# BW1097_BootSel.net
KiCad netlist of a schematic drawn in Altium Designer
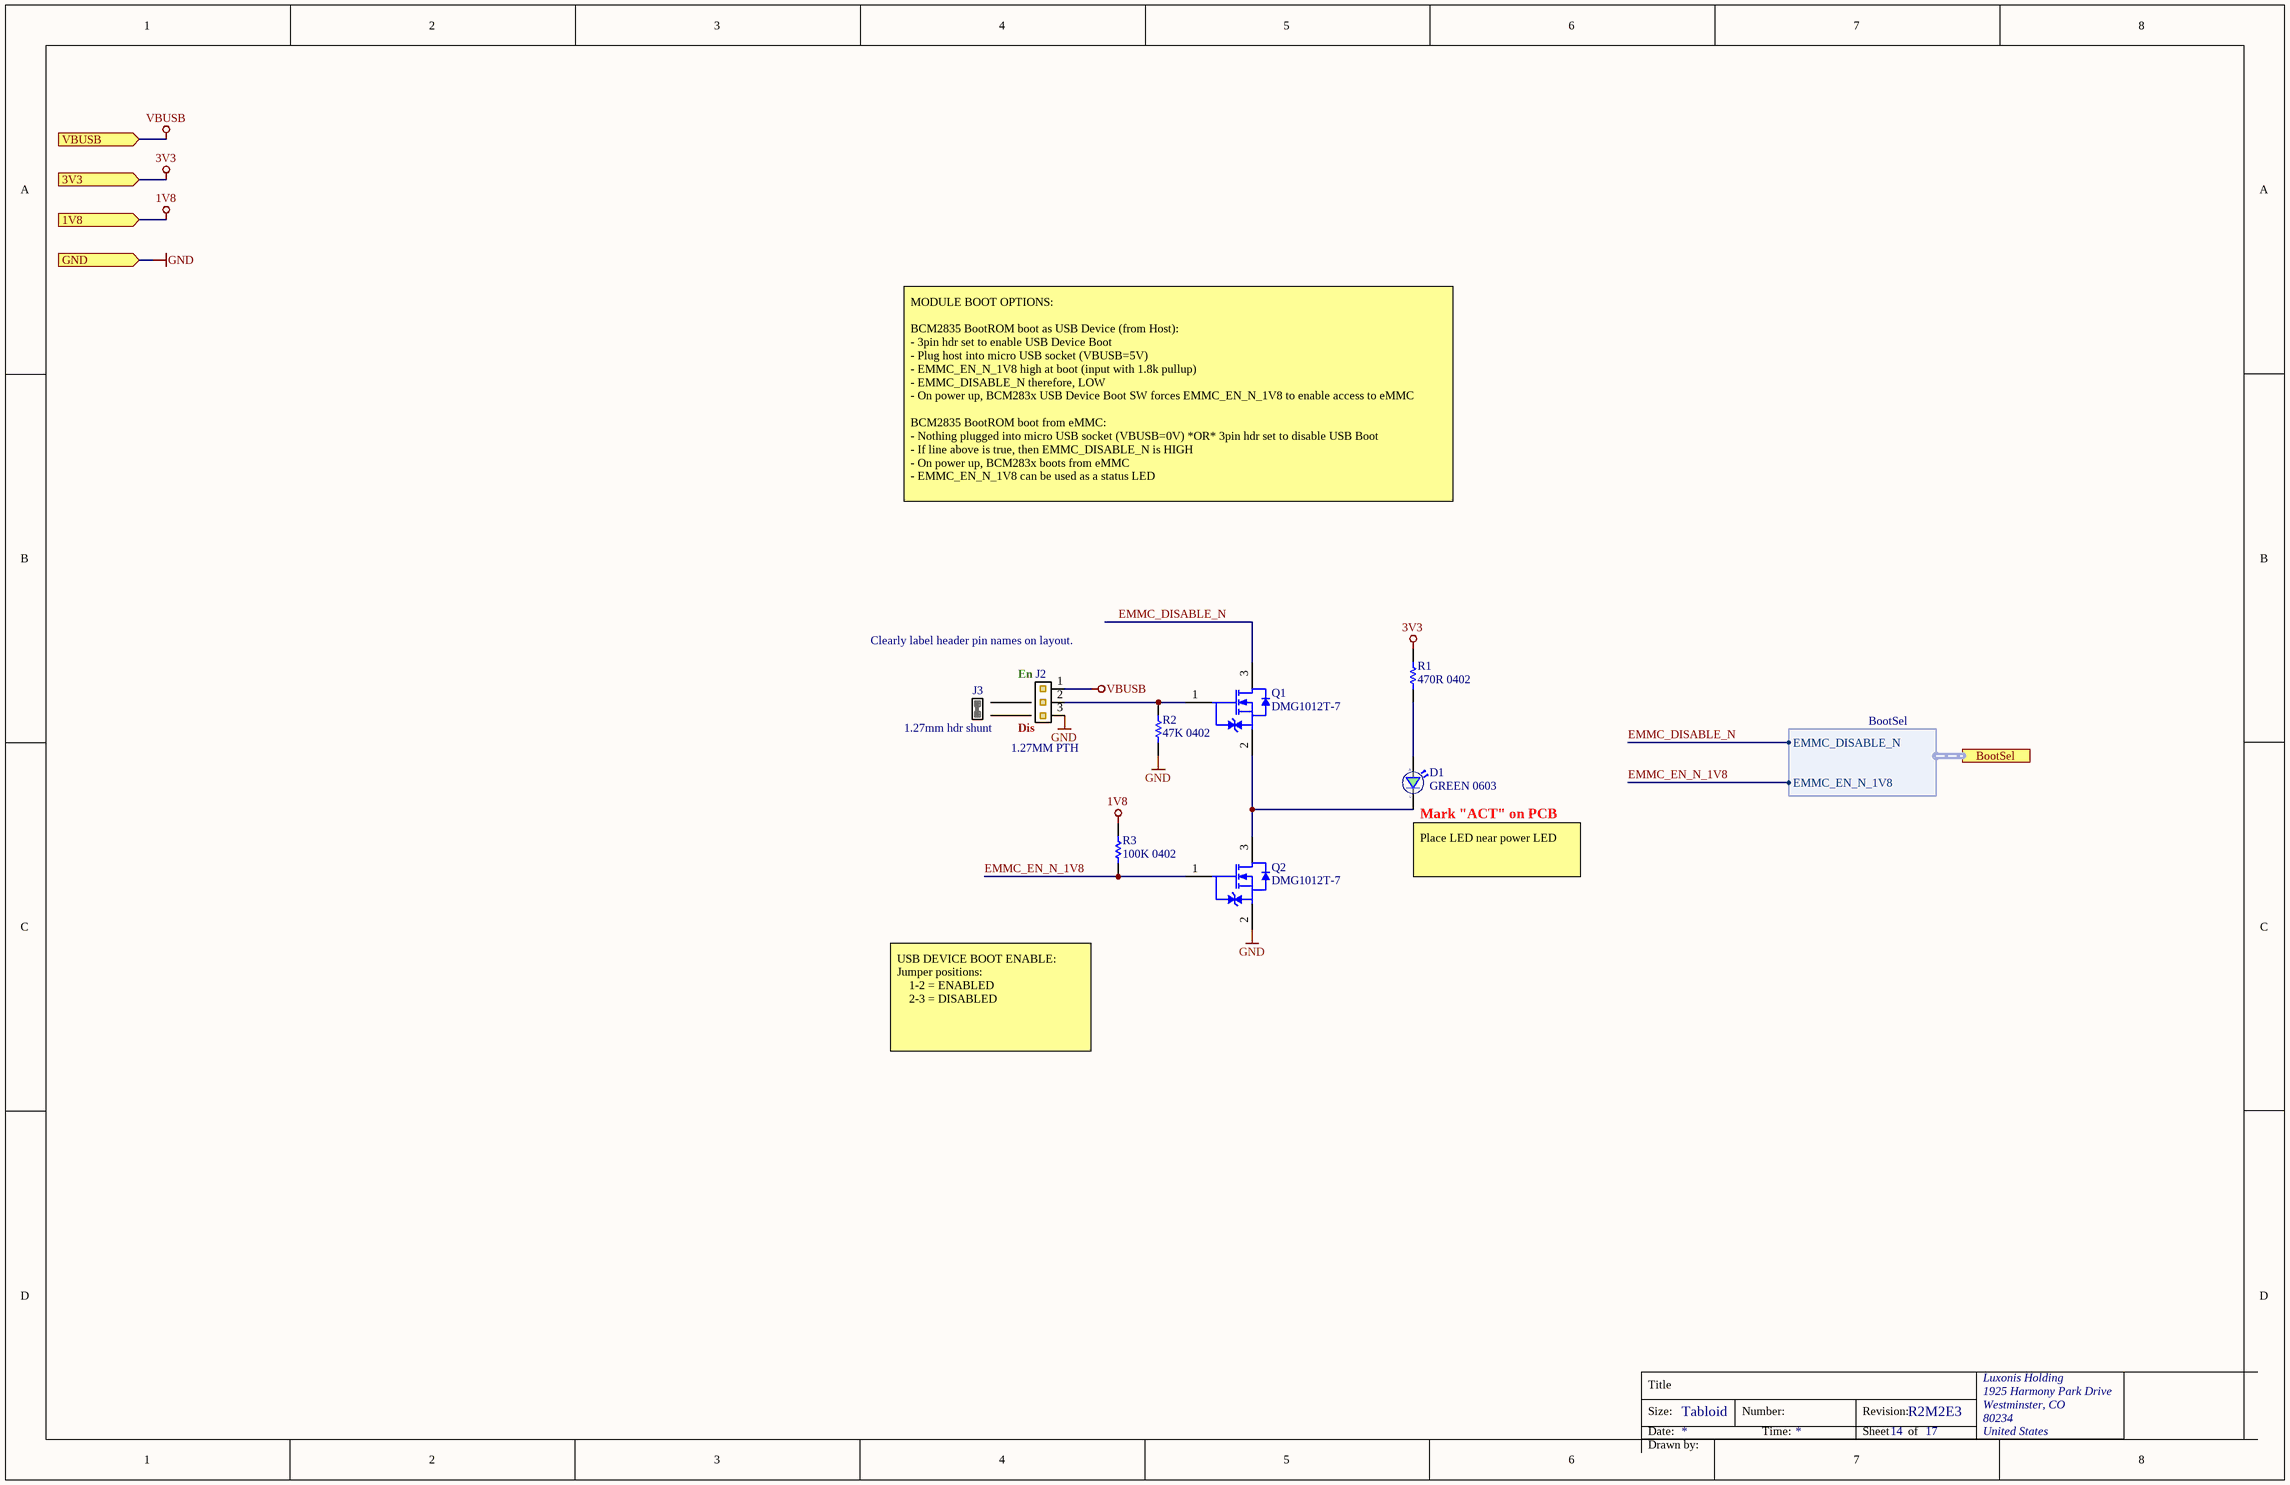
[diagram p0: BW1097_BootSel.SchDoc]

(export (version "E")
  (design (tool "Eeschema 10.0.6"))
  (components
    (comp (ref "D1")
      (value "GREEN 0603")
      (footprint "LuxonisMaster:SML_D1xx8W")
      (description "LED GREEN DIFFUSED 0603 SMD Green 572nm LED Indication - Discrete 2.2V 0603 (1608 Metric)")
      (fields (field (name "MANUFACTURER") "Rohm") (field (name "MANUFACTURER PART NUMBER") "SML-D12M8WT86"))
      (libsource (lib "LuxonisMaster") (part "SML-D12M8WT86"))
    )
    (comp (ref "J2")
      (value "1.27MM PTH")
      (footprint "LuxonisMaster:GRPB031VWVN-RC")
      (description "CONN HEADER VERT 3POS 1.27MM")
      (libsource (lib "LuxonisMaster") (part "GRPB031VWVN-RC"))
    )
    (comp (ref "J3")
      (value "1.27mm hdr shunt")
      (footprint "LuxonisMaster:M50-1900005")
      (description "CONN SHUNT 1.27MM BLACK")
      (libsource (lib "LuxonisMaster") (part "M50-1900005"))
    )
    (comp (ref "Q1")
      (value "DMG1012T-7")
      (footprint "LuxonisMaster:DMG1012T-7")
      (description "MOSFET N-CH 20V 630MA SOT-523")
      (libsource (lib "LuxonisMaster") (part "DMG1012T-7"))
    )
    (comp (ref "Q2")
      (value "DMG1012T-7")
      (footprint "LuxonisMaster:DMG1012T-7")
      (description "MOSFET N-CH 20V 630MA SOT-523")
      (libsource (lib "LuxonisMaster") (part "DMG1012T-7"))
    )
    (comp (ref "R1")
      (value "470R 0402")
      (footprint "RES_Altium_Vault_Generic:RESC0402(1005)_N")
      (description "RES SMD 470 OHM 1% 1/16W 0402")
      (fields (field (name "TOLERANCE") "1%"))
      (libsource (lib "LuxonisMaster") (part "CRCW0402470RFKED"))
    )
    (comp (ref "R2")
      (value "47K 0402")
      (footprint "RES_Altium_Vault_Generic:RESC0402(1005)_N")
      (description "RES SMD 47K OHM 1% 1/16W 0402")
      (fields (field (name "TOLERANCE") "1%"))
      (libsource (lib "LuxonisMaster") (part "RC0402FR-0747KL"))
    )
    (comp (ref "R3")
      (value "100K 0402")
      (footprint "RES_Altium_Vault_Generic:RESC0402(1005)_N")
      (description "RES SMD 100K OHM 1% 1/16W 0402")
      (fields (field (name "TOLERANCE") "1%"))
      (libsource (lib "LuxonisMaster") (part "RC0402FR-07100KL"))
    )
  )
  (nets
    (net (code "2") (name "/EMMC_DISABLE_N") (class "Default")
      (node (ref "Q1") (pin "3") (pinfunction "3_3") (pintype "passive"))
    )
    (net (code "3") (name "/EMMC_EN_N_1V8") (class "Default")
      (node (ref "Q2") (pin "1") (pinfunction "1_1") (pintype "passive"))
      (node (ref "R3") (pin "1") (pinfunction "1_1") (pintype "passive"))
    )
    (net (code "5") (name "1V8") (class "Default")
      (node (ref "R3") (pin "2") (pinfunction "2_2") (pintype "passive"))
    )
    (net (code "6") (name "3V3") (class "Default")
      (node (ref "R1") (pin "2") (pinfunction "2_2") (pintype "passive"))
    )
    (net (code "7") (name "GND") (class "Default")
      (node (ref "J2") (pin "3") (pinfunction "3_3") (pintype "passive"))
      (node (ref "Q2") (pin "2") (pinfunction "2_2") (pintype "passive"))
      (node (ref "R2") (pin "1") (pinfunction "1_1") (pintype "passive"))
    )
    (net (code "8") (name "Net-(D1-A)") (class "Default")
      (node (ref "D1") (pin "2") (pinfunction "A_2") (pintype "passive"))
      (node (ref "R1") (pin "1") (pinfunction "1_1") (pintype "passive"))
    )
    (net (code "9") (name "Net-(D1-C)") (class "Default")
      (node (ref "D1") (pin "1") (pinfunction "C_1") (pintype "passive"))
      (node (ref "Q1") (pin "2") (pinfunction "2_2") (pintype "passive"))
      (node (ref "Q2") (pin "3") (pinfunction "3_3") (pintype "passive"))
    )
    (net (code "10") (name "Net-(J2-Pad2)") (class "Default")
      (node (ref "J2") (pin "2") (pinfunction "2_2") (pintype "passive"))
      (node (ref "Q1") (pin "1") (pinfunction "1_1") (pintype "passive"))
      (node (ref "R2") (pin "2") (pinfunction "2_2") (pintype "passive"))
    )
    (net (code "11") (name "VBUSB") (class "Default")
      (node (ref "J2") (pin "1") (pinfunction "1_1") (pintype "passive"))
    )
  )
)
